# gt-jtx-m32-ver1_0.net
KiCad netlist of a schematic drawn in EAGLE
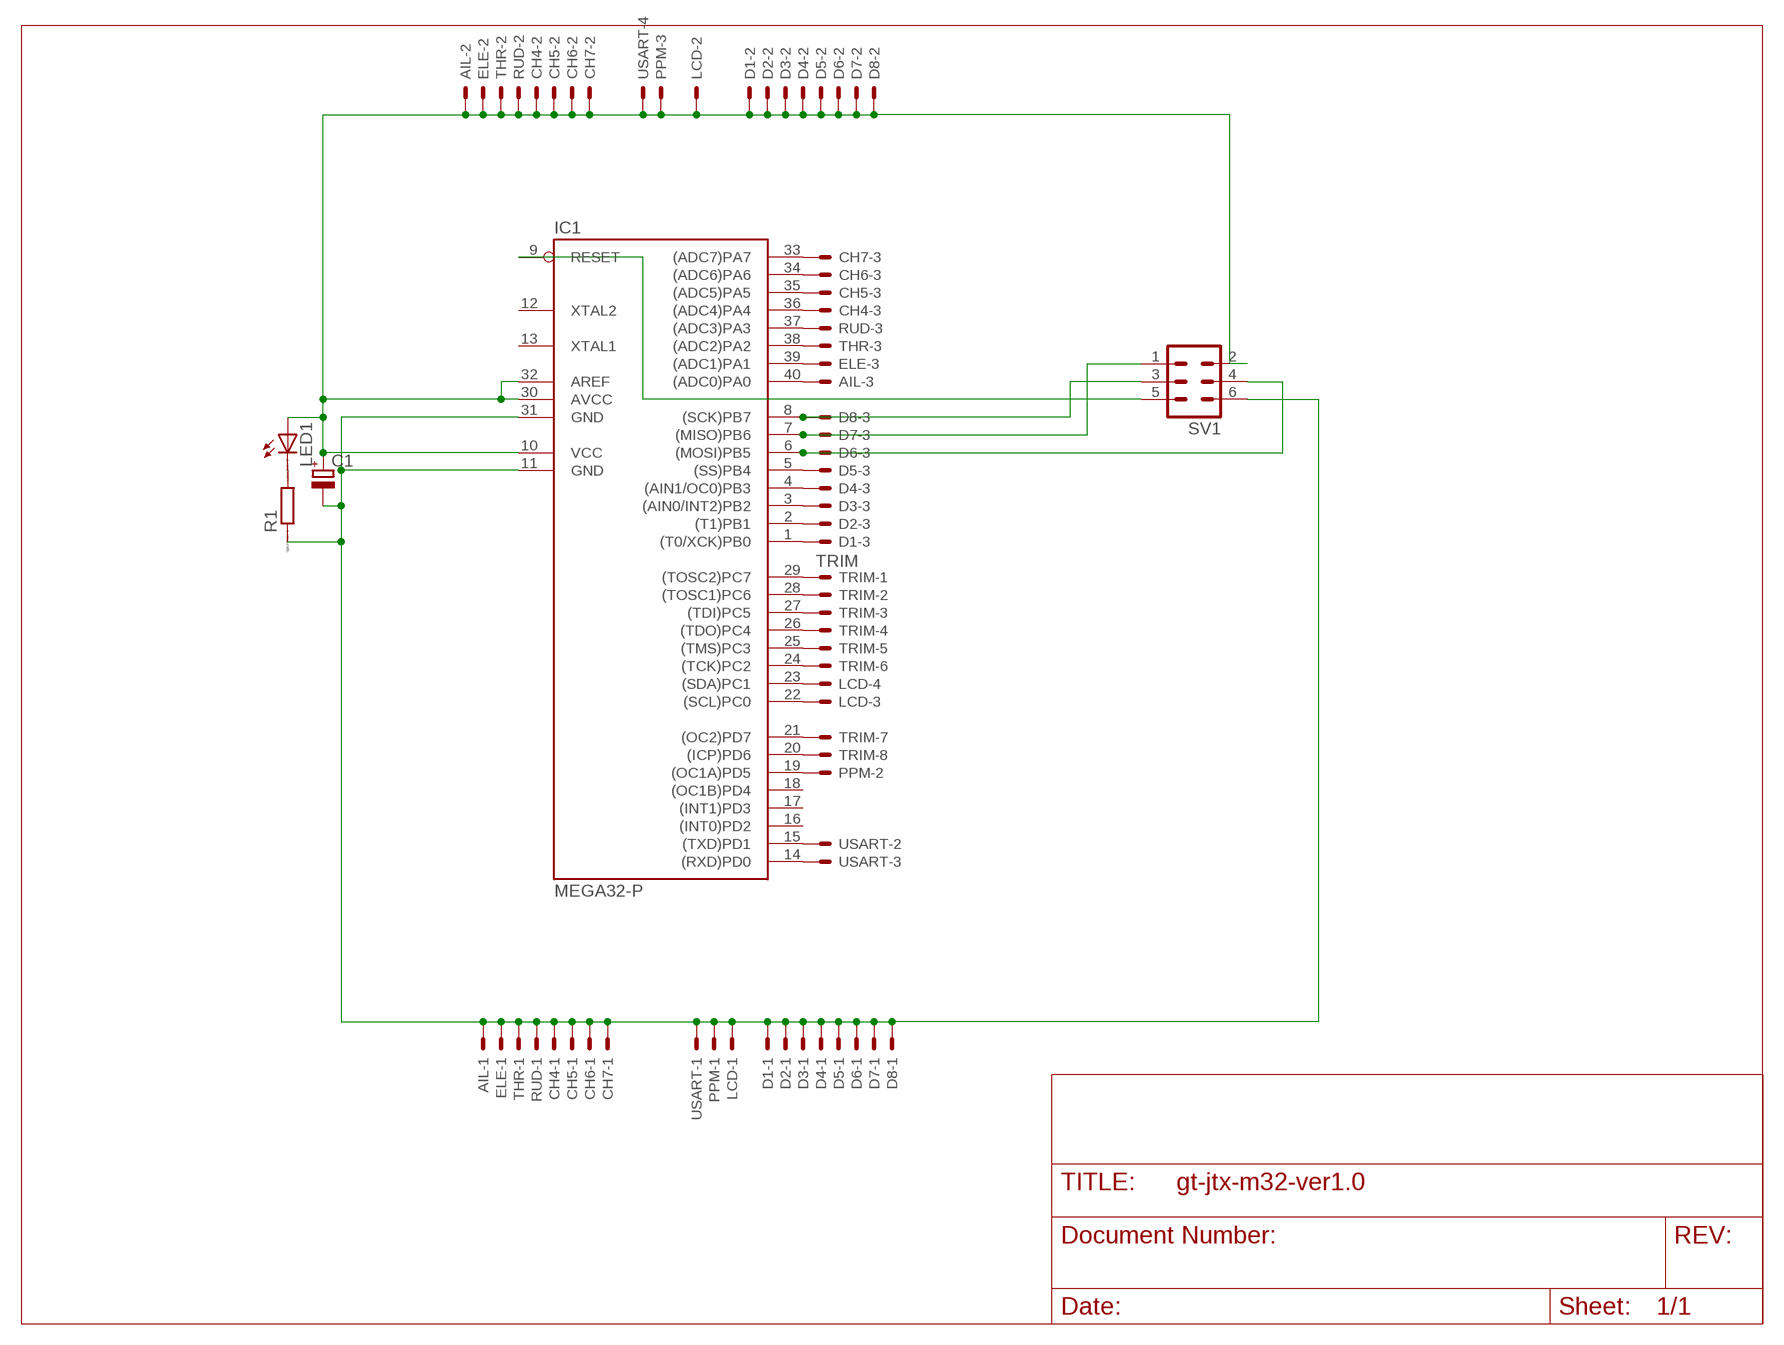
[diagram p0: schematic, sheet 1]

(export (version "E")
  (design (tool "Eeschema 10.0.6"))
  (components
    (comp (ref "AIL")
      (value "JST-XH-03-PIN-LONG-PAD")
      (footprint "eagle-import:JST-XH-03-PACKAGE-LONG-PAD")
      (libsource (lib "eagle-import") (part "JST-XH-03-PIN-LONG-PAD"))
    )
    (comp (ref "C1")
      (value "CPOL-EUC")
      (footprint "eagle-import:PANASONIC_C")
      (libsource (lib "eagle-import") (part "CPOL-EUC"))
    )
    (comp (ref "CH4")
      (value "JST-XH-03-PIN-LONG-PAD")
      (footprint "eagle-import:JST-XH-03-PACKAGE-LONG-PAD")
      (libsource (lib "eagle-import") (part "JST-XH-03-PIN-LONG-PAD"))
    )
    (comp (ref "CH5")
      (value "JST-XH-03-PIN-LONG-PAD")
      (footprint "eagle-import:JST-XH-03-PACKAGE-LONG-PAD")
      (libsource (lib "eagle-import") (part "JST-XH-03-PIN-LONG-PAD"))
    )
    (comp (ref "CH6")
      (value "JST-XH-03-PIN-LONG-PAD")
      (footprint "eagle-import:JST-XH-03-PACKAGE-LONG-PAD")
      (libsource (lib "eagle-import") (part "JST-XH-03-PIN-LONG-PAD"))
    )
    (comp (ref "CH7")
      (value "JST-XH-03-PIN-LONG-PAD")
      (footprint "eagle-import:JST-XH-03-PACKAGE-LONG-PAD")
      (libsource (lib "eagle-import") (part "JST-XH-03-PIN-LONG-PAD"))
    )
    (comp (ref "D1")
      (value "JST-XH-03-PIN-LONG-PAD")
      (footprint "eagle-import:JST-XH-03-PACKAGE-LONG-PAD")
      (libsource (lib "eagle-import") (part "JST-XH-03-PIN-LONG-PAD"))
    )
    (comp (ref "D2")
      (value "JST-XH-03-PIN-LONG-PAD")
      (footprint "eagle-import:JST-XH-03-PACKAGE-LONG-PAD")
      (libsource (lib "eagle-import") (part "JST-XH-03-PIN-LONG-PAD"))
    )
    (comp (ref "D3")
      (value "JST-XH-03-PIN-LONG-PAD")
      (footprint "eagle-import:JST-XH-03-PACKAGE-LONG-PAD")
      (libsource (lib "eagle-import") (part "JST-XH-03-PIN-LONG-PAD"))
    )
    (comp (ref "D4")
      (value "JST-XH-03-PIN-LONG-PAD")
      (footprint "eagle-import:JST-XH-03-PACKAGE-LONG-PAD")
      (libsource (lib "eagle-import") (part "JST-XH-03-PIN-LONG-PAD"))
    )
    (comp (ref "D5")
      (value "JST-XH-03-PIN-LONG-PAD")
      (footprint "eagle-import:JST-XH-03-PACKAGE-LONG-PAD")
      (libsource (lib "eagle-import") (part "JST-XH-03-PIN-LONG-PAD"))
    )
    (comp (ref "D6")
      (value "JST-XH-03-PIN-LONG-PAD")
      (footprint "eagle-import:JST-XH-03-PACKAGE-LONG-PAD")
      (libsource (lib "eagle-import") (part "JST-XH-03-PIN-LONG-PAD"))
    )
    (comp (ref "D7")
      (value "JST-XH-03-PIN-LONG-PAD")
      (footprint "eagle-import:JST-XH-03-PACKAGE-LONG-PAD")
      (libsource (lib "eagle-import") (part "JST-XH-03-PIN-LONG-PAD"))
    )
    (comp (ref "D8")
      (value "JST-XH-03-PIN-LONG-PAD")
      (footprint "eagle-import:JST-XH-03-PACKAGE-LONG-PAD")
      (libsource (lib "eagle-import") (part "JST-XH-03-PIN-LONG-PAD"))
    )
    (comp (ref "ELE")
      (value "JST-XH-03-PIN-LONG-PAD")
      (footprint "eagle-import:JST-XH-03-PACKAGE-LONG-PAD")
      (libsource (lib "eagle-import") (part "JST-XH-03-PIN-LONG-PAD"))
    )
    (comp (ref "IC1")
      (value "MEGA32-P")
      (footprint "eagle-import:DIL40")
      (fields (field (name "MPN") "ATMEGA32-16PU"))
      (libsource (lib "eagle-import") (part "MEGA32-P"))
    )
    (comp (ref "LCD")
      (value "JST-XH-04-PIN-LONG-PAD")
      (footprint "eagle-import:JST-XH-04-PACKAGE-LONG-PAD")
      (libsource (lib "eagle-import") (part "JST-XH-04-PIN-LONG-PAD"))
    )
    (comp (ref "LED1")
      (value "LED5MM")
      (footprint "eagle-import:LED5MM")
      (libsource (lib "eagle-import") (part "LED5MM"))
    )
    (comp (ref "PPM")
      (value "JST-XH-03-PIN-LONG-PAD")
      (footprint "eagle-import:JST-XH-03-PACKAGE-LONG-PAD")
      (libsource (lib "eagle-import") (part "JST-XH-03-PIN-LONG-PAD"))
    )
    (comp (ref "R1")
      (value "R0204/7")
      (footprint "eagle-import:0204_7")
      (libsource (lib "eagle-import") (part "R0204/7"))
    )
    (comp (ref "RUD")
      (value "JST-XH-03-PIN-LONG-PAD")
      (footprint "eagle-import:JST-XH-03-PACKAGE-LONG-PAD")
      (libsource (lib "eagle-import") (part "JST-XH-03-PIN-LONG-PAD"))
    )
    (comp (ref "SV1")
      (value "MA03-2")
      (footprint "eagle-import:MA03-2")
      (libsource (lib "eagle-import") (part "MA03-2"))
    )
    (comp (ref "THR")
      (value "JST-XH-03-PIN-LONG-PAD")
      (footprint "eagle-import:JST-XH-03-PACKAGE-LONG-PAD")
      (libsource (lib "eagle-import") (part "JST-XH-03-PIN-LONG-PAD"))
    )
    (comp (ref "TRIM")
      (value "TRIM")
      (footprint "eagle-import:JST-XH-08-PACKAGE-LONG-PAD")
      (libsource (lib "eagle-import") (part "JST-XH-08-PIN-LONG-PAD"))
    )
    (comp (ref "USART")
      (value "JST-XH-04-PIN-LONG-PAD")
      (footprint "eagle-import:JST-XH-04-PACKAGE-LONG-PAD")
      (libsource (lib "eagle-import") (part "JST-XH-04-PIN-LONG-PAD"))
    )
  )
  (nets
    (net (code "1") (name "Net-(AILA-S)") (class "Default")
      (node (ref "AIL") (pin "1") (pinfunction "S_1") (pintype "passive"))
      (node (ref "C1") (pin "-") (pinfunction "-_-") (pintype "passive"))
      (node (ref "CH4") (pin "1") (pinfunction "S_1") (pintype "passive"))
      (node (ref "CH5") (pin "1") (pinfunction "S_1") (pintype "passive"))
      (node (ref "CH6") (pin "1") (pinfunction "S_1") (pintype "passive"))
      (node (ref "CH7") (pin "1") (pinfunction "S_1") (pintype "passive"))
      (node (ref "D1") (pin "1") (pinfunction "S_1") (pintype "passive"))
      (node (ref "D2") (pin "1") (pinfunction "S_1") (pintype "passive"))
      (node (ref "D3") (pin "1") (pinfunction "S_1") (pintype "passive"))
      (node (ref "D4") (pin "1") (pinfunction "S_1") (pintype "passive"))
      (node (ref "D5") (pin "1") (pinfunction "S_1") (pintype "passive"))
      (node (ref "D6") (pin "1") (pinfunction "S_1") (pintype "passive"))
      (node (ref "D7") (pin "1") (pinfunction "S_1") (pintype "passive"))
      (node (ref "D8") (pin "1") (pinfunction "S_1") (pintype "passive"))
      (node (ref "ELE") (pin "1") (pinfunction "S_1") (pintype "passive"))
      (node (ref "IC1") (pin "11") (pinfunction "GND_11") (pintype "power_in"))
      (node (ref "IC1") (pin "31") (pinfunction "GND_31") (pintype "power_in"))
      (node (ref "LCD") (pin "1") (pinfunction "S_1") (pintype "passive"))
      (node (ref "PPM") (pin "1") (pinfunction "S_1") (pintype "passive"))
      (node (ref "R1") (pin "1") (pinfunction "1_1") (pintype "passive"))
      (node (ref "RUD") (pin "1") (pinfunction "S_1") (pintype "passive"))
      (node (ref "SV1") (pin "6") (pinfunction "6_6") (pintype "passive"))
      (node (ref "THR") (pin "1") (pinfunction "S_1") (pintype "passive"))
      (node (ref "USART") (pin "1") (pinfunction "S_1") (pintype "passive"))
    )
    (net (code "2") (name "Net-(AILB-S)") (class "Default")
      (node (ref "AIL") (pin "2") (pinfunction "S_2") (pintype "passive"))
      (node (ref "C1") (pin "+") (pinfunction "+_+") (pintype "passive"))
      (node (ref "CH4") (pin "2") (pinfunction "S_2") (pintype "passive"))
      (node (ref "CH5") (pin "2") (pinfunction "S_2") (pintype "passive"))
      (node (ref "CH6") (pin "2") (pinfunction "S_2") (pintype "passive"))
      (node (ref "CH7") (pin "2") (pinfunction "S_2") (pintype "passive"))
      (node (ref "D1") (pin "2") (pinfunction "S_2") (pintype "passive"))
      (node (ref "D2") (pin "2") (pinfunction "S_2") (pintype "passive"))
      (node (ref "D3") (pin "2") (pinfunction "S_2") (pintype "passive"))
      (node (ref "D4") (pin "2") (pinfunction "S_2") (pintype "passive"))
      (node (ref "D5") (pin "2") (pinfunction "S_2") (pintype "passive"))
      (node (ref "D6") (pin "2") (pinfunction "S_2") (pintype "passive"))
      (node (ref "D7") (pin "2") (pinfunction "S_2") (pintype "passive"))
      (node (ref "D8") (pin "2") (pinfunction "S_2") (pintype "passive"))
      (node (ref "ELE") (pin "2") (pinfunction "S_2") (pintype "passive"))
      (node (ref "IC1") (pin "10") (pinfunction "VCC_10") (pintype "power_in"))
      (node (ref "IC1") (pin "30") (pinfunction "AVCC_30") (pintype "power_in"))
      (node (ref "IC1") (pin "32") (pinfunction "AREF_32") (pintype "passive"))
      (node (ref "LCD") (pin "2") (pinfunction "S_2") (pintype "passive"))
      (node (ref "LED1") (pin "A") (pinfunction "A_A") (pintype "passive"))
      (node (ref "PPM") (pin "3") (pinfunction "S_3") (pintype "passive"))
      (node (ref "RUD") (pin "2") (pinfunction "S_2") (pintype "passive"))
      (node (ref "SV1") (pin "2") (pinfunction "2_2") (pintype "passive"))
      (node (ref "THR") (pin "2") (pinfunction "S_2") (pintype "passive"))
      (node (ref "USART") (pin "4") (pinfunction "S_4") (pintype "passive"))
    )
    (net (code "3") (name "Net-(AILC-S)") (class "Default")
      (node (ref "AIL") (pin "3") (pinfunction "S_3") (pintype "passive"))
      (node (ref "IC1") (pin "40") (pinfunction "(ADC0)PA0_40") (pintype "bidirectional"))
    )
    (net (code "4") (name "Net-(CH4C-S)") (class "Default")
      (node (ref "CH4") (pin "3") (pinfunction "S_3") (pintype "passive"))
      (node (ref "IC1") (pin "36") (pinfunction "(ADC4)PA4_36") (pintype "bidirectional"))
    )
    (net (code "5") (name "Net-(CH5C-S)") (class "Default")
      (node (ref "CH5") (pin "3") (pinfunction "S_3") (pintype "passive"))
      (node (ref "IC1") (pin "35") (pinfunction "(ADC5)PA5_35") (pintype "bidirectional"))
    )
    (net (code "6") (name "Net-(CH6C-S)") (class "Default")
      (node (ref "CH6") (pin "3") (pinfunction "S_3") (pintype "passive"))
      (node (ref "IC1") (pin "34") (pinfunction "(ADC6)PA6_34") (pintype "bidirectional"))
    )
    (net (code "7") (name "Net-(CH7C-S)") (class "Default")
      (node (ref "CH7") (pin "3") (pinfunction "S_3") (pintype "passive"))
      (node (ref "IC1") (pin "33") (pinfunction "(ADC7)PA7_33") (pintype "bidirectional"))
    )
    (net (code "8") (name "Net-(D1C-S)") (class "Default")
      (node (ref "D1") (pin "3") (pinfunction "S_3") (pintype "passive"))
      (node (ref "IC1") (pin "1") (pinfunction "(T0/XCK)PB0_1") (pintype "bidirectional"))
    )
    (net (code "9") (name "Net-(D2C-S)") (class "Default")
      (node (ref "D2") (pin "3") (pinfunction "S_3") (pintype "passive"))
      (node (ref "IC1") (pin "2") (pinfunction "(T1)PB1_2") (pintype "bidirectional"))
    )
    (net (code "10") (name "Net-(D3C-S)") (class "Default")
      (node (ref "D3") (pin "3") (pinfunction "S_3") (pintype "passive"))
      (node (ref "IC1") (pin "3") (pinfunction "(AIN0/INT2)PB2_3") (pintype "bidirectional"))
    )
    (net (code "11") (name "Net-(D4C-S)") (class "Default")
      (node (ref "D4") (pin "3") (pinfunction "S_3") (pintype "passive"))
      (node (ref "IC1") (pin "4") (pinfunction "(AIN1/OC0)PB3_4") (pintype "bidirectional"))
    )
    (net (code "12") (name "Net-(D5C-S)") (class "Default")
      (node (ref "D5") (pin "3") (pinfunction "S_3") (pintype "passive"))
      (node (ref "IC1") (pin "5") (pinfunction "(SS)PB4_5") (pintype "bidirectional"))
    )
    (net (code "13") (name "Net-(D6C-S)") (class "Default")
      (node (ref "D6") (pin "3") (pinfunction "S_3") (pintype "passive"))
      (node (ref "IC1") (pin "6") (pinfunction "(MOSI)PB5_6") (pintype "bidirectional"))
      (node (ref "SV1") (pin "4") (pinfunction "4_4") (pintype "passive"))
    )
    (net (code "14") (name "Net-(D7C-S)") (class "Default")
      (node (ref "D7") (pin "3") (pinfunction "S_3") (pintype "passive"))
      (node (ref "IC1") (pin "7") (pinfunction "(MISO)PB6_7") (pintype "bidirectional"))
      (node (ref "SV1") (pin "1") (pinfunction "1_1") (pintype "passive"))
    )
    (net (code "15") (name "Net-(D8C-S)") (class "Default")
      (node (ref "D8") (pin "3") (pinfunction "S_3") (pintype "passive"))
      (node (ref "IC1") (pin "8") (pinfunction "(SCK)PB7_8") (pintype "bidirectional"))
      (node (ref "SV1") (pin "3") (pinfunction "3_3") (pintype "passive"))
    )
    (net (code "16") (name "Net-(ELEC-S)") (class "Default")
      (node (ref "ELE") (pin "3") (pinfunction "S_3") (pintype "passive"))
      (node (ref "IC1") (pin "39") (pinfunction "(ADC1)PA1_39") (pintype "bidirectional"))
    )
    (net (code "17") (name "Net-(IC1-(ADC2)PA2)") (class "Default")
      (node (ref "IC1") (pin "38") (pinfunction "(ADC2)PA2_38") (pintype "bidirectional"))
      (node (ref "THR") (pin "3") (pinfunction "S_3") (pintype "passive"))
    )
    (net (code "18") (name "Net-(IC1-(ADC3)PA3)") (class "Default")
      (node (ref "IC1") (pin "37") (pinfunction "(ADC3)PA3_37") (pintype "bidirectional"))
      (node (ref "RUD") (pin "3") (pinfunction "S_3") (pintype "passive"))
    )
    (net (code "19") (name "Net-(IC1-(ICP)PD6)") (class "Default")
      (node (ref "IC1") (pin "20") (pinfunction "(ICP)PD6_20") (pintype "bidirectional"))
      (node (ref "TRIM") (pin "8") (pinfunction "S_8") (pintype "passive"))
    )
    (net (code "20") (name "Net-(IC1-(OC1A)PD5)") (class "Default")
      (node (ref "IC1") (pin "19") (pinfunction "(OC1A)PD5_19") (pintype "bidirectional"))
      (node (ref "PPM") (pin "2") (pinfunction "S_2") (pintype "passive"))
    )
    (net (code "21") (name "Net-(IC1-(OC2)PD7)") (class "Default")
      (node (ref "IC1") (pin "21") (pinfunction "(OC2)PD7_21") (pintype "bidirectional"))
      (node (ref "TRIM") (pin "7") (pinfunction "S_7") (pintype "passive"))
    )
    (net (code "22") (name "Net-(IC1-(RXD)PD0)") (class "Default")
      (node (ref "IC1") (pin "14") (pinfunction "(RXD)PD0_14") (pintype "bidirectional"))
      (node (ref "USART") (pin "3") (pinfunction "S_3") (pintype "passive"))
    )
    (net (code "23") (name "Net-(IC1-(SCL)PC0)") (class "Default")
      (node (ref "IC1") (pin "22") (pinfunction "(SCL)PC0_22") (pintype "bidirectional"))
      (node (ref "LCD") (pin "3") (pinfunction "S_3") (pintype "passive"))
    )
    (net (code "24") (name "Net-(IC1-(SDA)PC1)") (class "Default")
      (node (ref "IC1") (pin "23") (pinfunction "(SDA)PC1_23") (pintype "bidirectional"))
      (node (ref "LCD") (pin "4") (pinfunction "S_4") (pintype "passive"))
    )
    (net (code "25") (name "Net-(IC1-(TCK)PC2)") (class "Default")
      (node (ref "IC1") (pin "24") (pinfunction "(TCK)PC2_24") (pintype "bidirectional"))
      (node (ref "TRIM") (pin "6") (pinfunction "S_6") (pintype "passive"))
    )
    (net (code "26") (name "Net-(IC1-(TDI)PC5)") (class "Default")
      (node (ref "IC1") (pin "27") (pinfunction "(TDI)PC5_27") (pintype "bidirectional"))
      (node (ref "TRIM") (pin "3") (pinfunction "S_3") (pintype "passive"))
    )
    (net (code "27") (name "Net-(IC1-(TDO)PC4)") (class "Default")
      (node (ref "IC1") (pin "26") (pinfunction "(TDO)PC4_26") (pintype "bidirectional"))
      (node (ref "TRIM") (pin "4") (pinfunction "S_4") (pintype "passive"))
    )
    (net (code "28") (name "Net-(IC1-(TMS)PC3)") (class "Default")
      (node (ref "IC1") (pin "25") (pinfunction "(TMS)PC3_25") (pintype "bidirectional"))
      (node (ref "TRIM") (pin "5") (pinfunction "S_5") (pintype "passive"))
    )
    (net (code "29") (name "Net-(IC1-(TOSC1)PC6)") (class "Default")
      (node (ref "IC1") (pin "28") (pinfunction "(TOSC1)PC6_28") (pintype "bidirectional"))
      (node (ref "TRIM") (pin "2") (pinfunction "S_2") (pintype "passive"))
    )
    (net (code "30") (name "Net-(IC1-(TOSC2)PC7)") (class "Default")
      (node (ref "IC1") (pin "29") (pinfunction "(TOSC2)PC7_29") (pintype "bidirectional"))
      (node (ref "TRIM") (pin "1") (pinfunction "S_1") (pintype "passive"))
    )
    (net (code "31") (name "Net-(IC1-(TXD)PD1)") (class "Default")
      (node (ref "IC1") (pin "15") (pinfunction "(TXD)PD1_15") (pintype "bidirectional"))
      (node (ref "USART") (pin "2") (pinfunction "S_2") (pintype "passive"))
    )
    (net (code "32") (name "Net-(IC1-RESET)") (class "Default")
      (node (ref "IC1") (pin "9") (pinfunction "RESET_9") (pintype "input"))
      (node (ref "SV1") (pin "5") (pinfunction "5_5") (pintype "passive"))
    )
    (net (code "33") (name "Net-(LED1-C)") (class "Default")
      (node (ref "LED1") (pin "K") (pinfunction "C_K") (pintype "passive"))
      (node (ref "R1") (pin "2") (pinfunction "2_2") (pintype "passive"))
    )
    (net (code "34") (name "unconnected-(IC1-(INT0)PD2-Pad16)") (class "Default")
      (node (ref "IC1") (pin "16") (pinfunction "(INT0)PD2_16") (pintype "bidirectional"))
    )
    (net (code "35") (name "unconnected-(IC1-(INT1)PD3-Pad17)") (class "Default")
      (node (ref "IC1") (pin "17") (pinfunction "(INT1)PD3_17") (pintype "bidirectional"))
    )
    (net (code "36") (name "unconnected-(IC1-(OC1B)PD4-Pad18)") (class "Default")
      (node (ref "IC1") (pin "18") (pinfunction "(OC1B)PD4_18") (pintype "bidirectional"))
    )
    (net (code "37") (name "unconnected-(IC1-XTAL1-Pad13)") (class "Default")
      (node (ref "IC1") (pin "13") (pinfunction "XTAL1_13") (pintype "bidirectional"))
    )
    (net (code "38") (name "unconnected-(IC1-XTAL2-Pad12)") (class "Default")
      (node (ref "IC1") (pin "12") (pinfunction "XTAL2_12") (pintype "bidirectional"))
    )
  )
)
